# MicroMod_Processor_Board-nRF52840.net
KiCad netlist of a schematic drawn in EAGLE
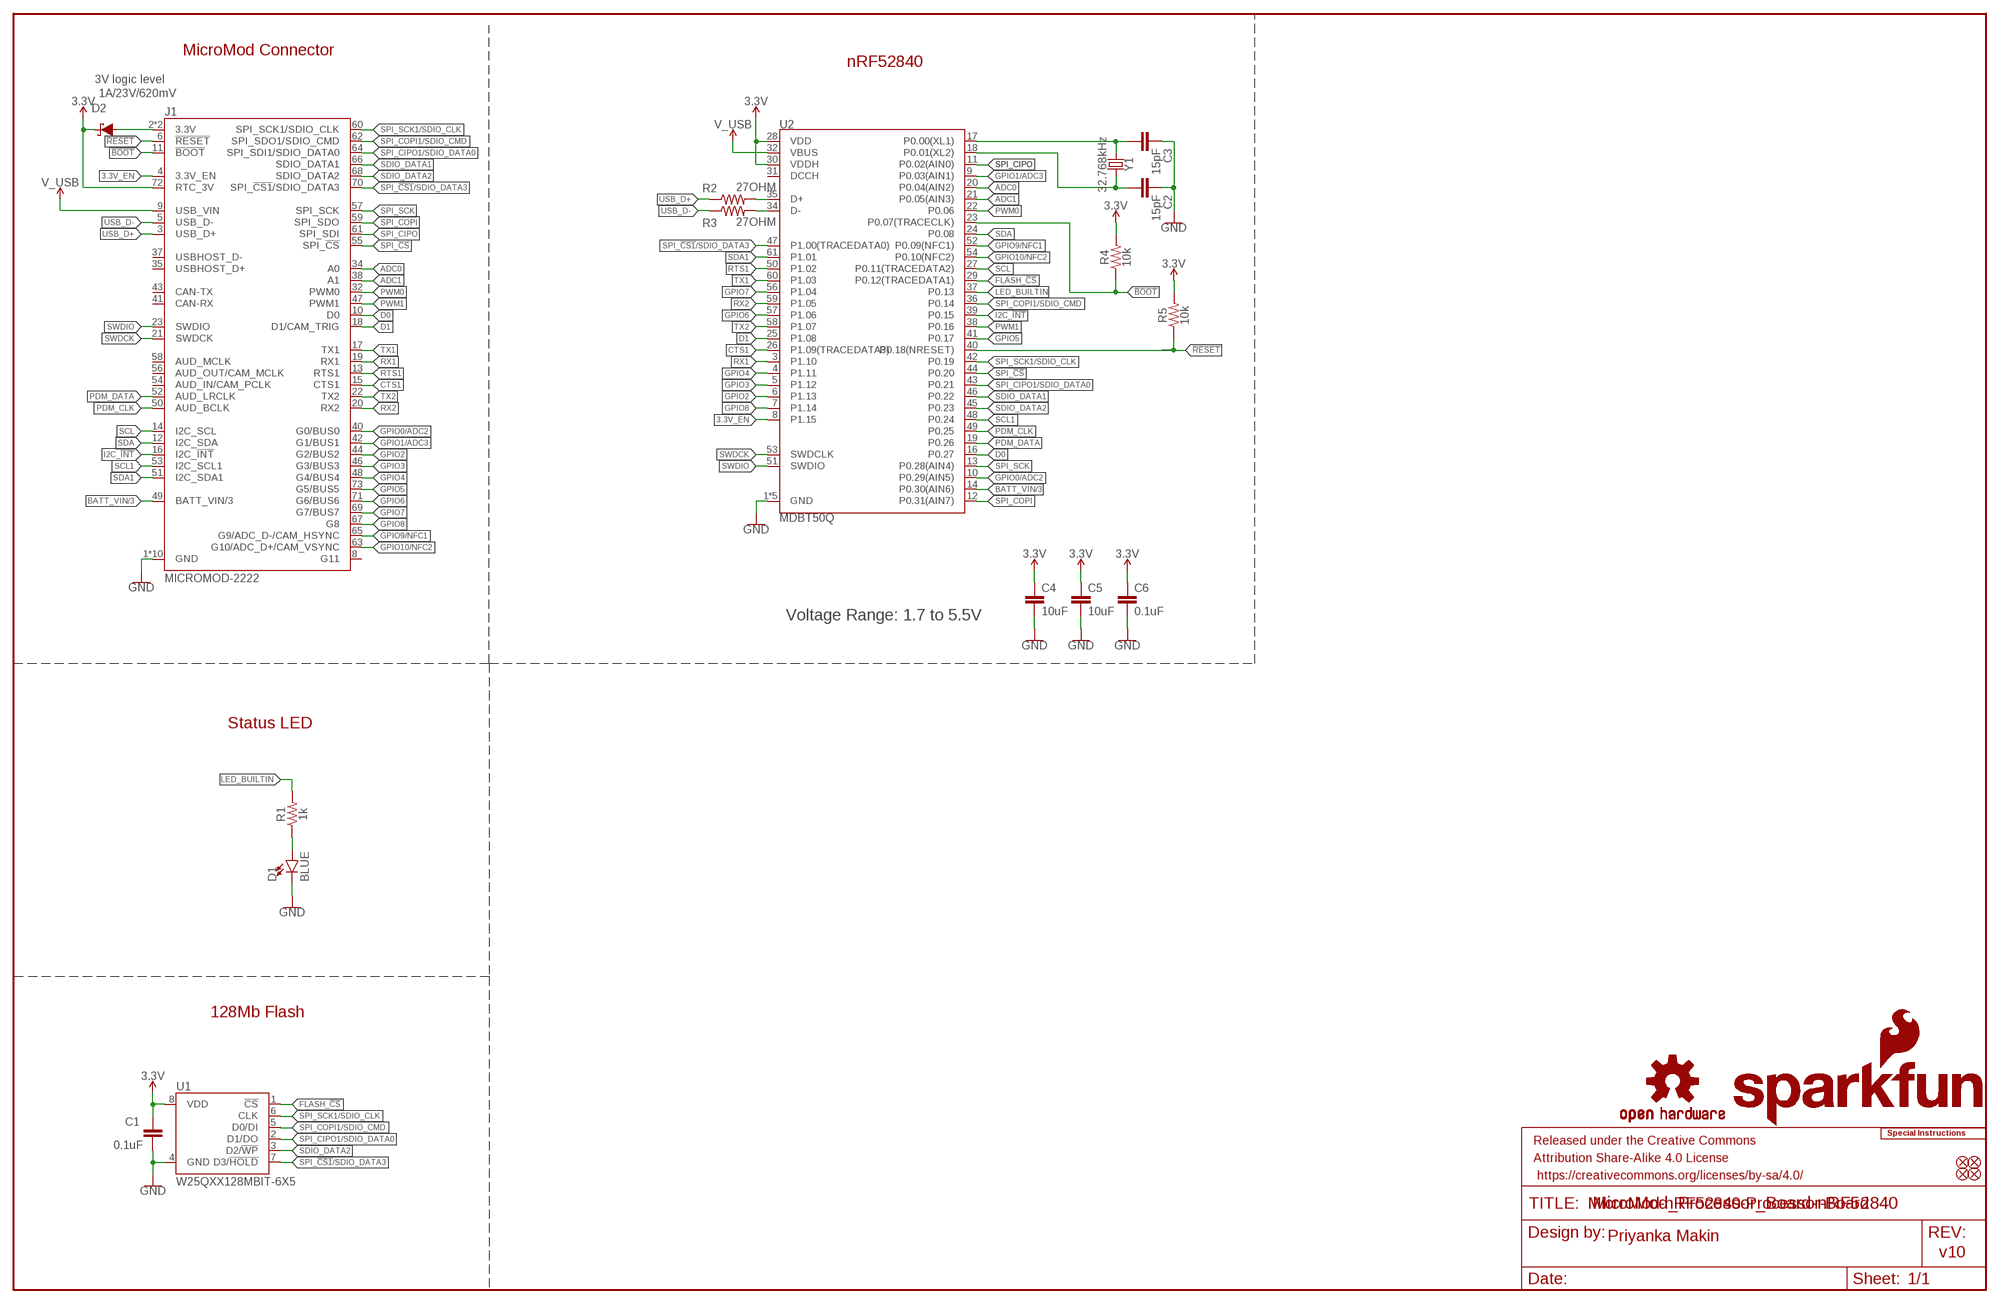
[diagram p0: schematic, sheet 1]

(export (version "E")
  (design (tool "Eeschema 10.0.6"))
  (components
    (comp (ref "C1")
      (value "0.1uF")
      (footprint "eagle-import:0402-TIGHT")
      (libsource (lib "eagle-import") (part "0.1UF-0402T-16V-10%"))
    )
    (comp (ref "C2")
      (value "15pF")
      (footprint "eagle-import:0402-TIGHT")
      (libsource (lib "eagle-import") (part "15PF-0402T-50V-5%"))
    )
    (comp (ref "C3")
      (value "15pF")
      (footprint "eagle-import:0402-TIGHT")
      (libsource (lib "eagle-import") (part "15PF-0402T-50V-5%"))
    )
    (comp (ref "C4")
      (value "10uF")
      (footprint "eagle-import:0402-TIGHT")
      (libsource (lib "eagle-import") (part "10UF-0402T-6.3V-20%"))
    )
    (comp (ref "C5")
      (value "10uF")
      (footprint "eagle-import:0402-TIGHT")
      (libsource (lib "eagle-import") (part "10UF-0402T-6.3V-20%"))
    )
    (comp (ref "C6")
      (value "0.1uF")
      (footprint "eagle-import:0402-TIGHT")
      (libsource (lib "eagle-import") (part "0.1UF-0402T-16V-10%"))
    )
    (comp (ref "D1")
      (value "BLUE")
      (footprint "eagle-import:LED-0603")
      (libsource (lib "eagle-import") (part "LED-BLUE0603"))
    )
    (comp (ref "D2")
      (value "1A/23V/620mV")
      (footprint "eagle-import:SOD-323")
      (libsource (lib "eagle-import") (part "DIODE-SCHOTTKY-BAT20J"))
    )
    (comp (ref "FD1")
      (value "FIDUCIALUFIDUCIAL")
      (footprint "eagle-import:FIDUCIAL-MICRO")
      (libsource (lib "eagle-import") (part "FIDUCIALUFIDUCIAL"))
    )
    (comp (ref "FD2")
      (value "FIDUCIALUFIDUCIAL")
      (footprint "eagle-import:FIDUCIAL-MICRO")
      (libsource (lib "eagle-import") (part "FIDUCIALUFIDUCIAL"))
    )
    (comp (ref "FD3")
      (value "FIDUCIALUFIDUCIAL")
      (footprint "eagle-import:FIDUCIAL-MICRO")
      (libsource (lib "eagle-import") (part "FIDUCIALUFIDUCIAL"))
    )
    (comp (ref "FD4")
      (value "FIDUCIALUFIDUCIAL")
      (footprint "eagle-import:FIDUCIAL-MICRO")
      (libsource (lib "eagle-import") (part "FIDUCIALUFIDUCIAL"))
    )
    (comp (ref "FRAME1")
      (value "FRAME-LEDGER")
      (footprint "eagle-import:CREATIVE_COMMONS")
      (libsource (lib "eagle-import") (part "FRAME-LEDGER"))
    )
    (comp (ref "J1")
      (value "MICROMOD-2222")
      (footprint "eagle-import:M.2-CARD-E-22")
      (libsource (lib "eagle-import") (part "MICROMOD-2222"))
    )
    (comp (ref "LOGO1")
      (value "SFE_LOGO_NAME_FLAME.1_INCH")
      (footprint "eagle-import:SFE_LOGO_NAME_FLAME_.1")
      (libsource (lib "eagle-import") (part "SFE_LOGO_NAME_FLAME.1_INCH"))
    )
    (comp (ref "LOGO2")
      (value "SFE_LOGO_FLAME.1_INCH")
      (footprint "eagle-import:SFE_LOGO_FLAME_.1")
      (libsource (lib "eagle-import") (part "SFE_LOGO_FLAME.1_INCH"))
    )
    (comp (ref "LOGO3")
      (value "OSHW-LOGOMINI")
      (footprint "eagle-import:OSHW-LOGO-MINI")
      (libsource (lib "eagle-import") (part "OSHW-LOGOMINI"))
    )
    (comp (ref "LOGO4")
      (value "SPECIAL_INSTRUCTIONS-ORDERING")
      (footprint "eagle-import:ORDERING_INSTRUCTIONS")
      (libsource (lib "eagle-import") (part "SPECIAL_INSTRUCTIONS-ORDERING"))
    )
    (comp (ref "R1")
      (value "1k")
      (footprint "eagle-import:0402-TIGHT")
      (libsource (lib "eagle-import") (part "1KOHM-0402T-1/16W-1%"))
    )
    (comp (ref "R2")
      (value "27OHM")
      (footprint "eagle-import:0402-TIGHT")
      (libsource (lib "eagle-import") (part "27OHM"))
    )
    (comp (ref "R3")
      (value "27OHM")
      (footprint "eagle-import:0402-TIGHT")
      (libsource (lib "eagle-import") (part "27OHM"))
    )
    (comp (ref "R4")
      (value "10k")
      (footprint "eagle-import:0402-TIGHT")
      (libsource (lib "eagle-import") (part "10KOHM-0402T-1/16W-1%"))
    )
    (comp (ref "R5")
      (value "10k")
      (footprint "eagle-import:0402-TIGHT")
      (libsource (lib "eagle-import") (part "10KOHM-0402T-1/16W-1%"))
    )
    (comp (ref "U1")
      (value "W25QXX128MBIT-6X5")
      (footprint "eagle-import:WSON-8-6X5")
      (libsource (lib "eagle-import") (part "W25QXX128MBIT-6X5"))
    )
    (comp (ref "U2")
      (value "MDBT50Q")
      (footprint "eagle-import:MDBT50Q")
      (libsource (lib "eagle-import") (part "MDBT50Q"))
    )
    (comp (ref "Y1")
      (value "32.768kHz")
      (footprint "eagle-import:CRYSTAL-SMD-3.2X1.5MM")
      (libsource (lib "eagle-import") (part "CRYSTAL-32.768KHZSMD-3.2X1.5"))
    )
  )
  (nets
    (net (code "1") (name "/FLASH_~{CS}") (class "Default")
      (node (ref "U1") (pin "1") (pinfunction "~{CS}_1") (pintype "bidirectional"))
      (node (ref "U2") (pin "29") (pinfunction "P0.12(TRACEDATA1)_29") (pintype "bidirectional"))
    )
    (net (code "2") (name "/I2C_~{INT}") (class "Default")
      (node (ref "J1") (pin "16") (pinfunction "I2C_~{INT}_16") (pintype "bidirectional"))
      (node (ref "U2") (pin "39") (pinfunction "P0.15_39") (pintype "bidirectional"))
    )
    (net (code "3") (name "/SPI_~{CS1}{slash}SDIO_DATA3") (class "Default")
      (node (ref "J1") (pin "70") (pinfunction "SPI_~{CS1}/SDIO_DATA3_70") (pintype "bidirectional"))
      (node (ref "U1") (pin "7") (pinfunction "D3/~{HOLD}_7") (pintype "bidirectional"))
      (node (ref "U2") (pin "47") (pinfunction "P1.00(TRACEDATA0)_47") (pintype "bidirectional"))
    )
    (net (code "4") (name "/SPI_~{CS}") (class "Default")
      (node (ref "J1") (pin "55") (pinfunction "SPI_~{CS}_55") (pintype "bidirectional"))
      (node (ref "U2") (pin "44") (pinfunction "P0.20_44") (pintype "bidirectional"))
    )
    (net (code "5") (name "/~{BOOT}") (class "Default")
      (node (ref "J1") (pin "11") (pinfunction "~{BOOT}_11") (pintype "bidirectional"))
      (node (ref "R4") (pin "1") (pinfunction "1_1") (pintype "passive"))
      (node (ref "U2") (pin "23") (pinfunction "P0.07(TRACECLK)_23") (pintype "bidirectional"))
    )
    (net (code "6") (name "/~{RESET}") (class "Default")
      (node (ref "J1") (pin "6") (pinfunction "~{RESET}_6") (pintype "bidirectional"))
      (node (ref "R5") (pin "1") (pinfunction "1_1") (pintype "passive"))
      (node (ref "U2") (pin "40") (pinfunction "P0.18(NRESET)_40") (pintype "bidirectional"))
    )
    (net (code "7") (name "3.3V") (class "Default")
      (node (ref "C1") (pin "1") (pinfunction "1_1") (pintype "passive"))
      (node (ref "C4") (pin "1") (pinfunction "1_1") (pintype "passive"))
      (node (ref "C5") (pin "1") (pinfunction "1_1") (pintype "passive"))
      (node (ref "C6") (pin "1") (pinfunction "1_1") (pintype "passive"))
      (node (ref "D2") (pin "C") (pinfunction "C_C") (pintype "passive"))
      (node (ref "J1") (pin "72") (pinfunction "RTC_3V_72") (pintype "bidirectional"))
      (node (ref "R4") (pin "2") (pinfunction "2_2") (pintype "passive"))
      (node (ref "R5") (pin "2") (pinfunction "2_2") (pintype "passive"))
      (node (ref "U1") (pin "8") (pinfunction "VDD_8") (pintype "bidirectional"))
      (node (ref "U2") (pin "28") (pinfunction "VDD_28") (pintype "bidirectional"))
      (node (ref "U2") (pin "30") (pinfunction "VDDH_30") (pintype "bidirectional"))
    )
    (net (code "8") (name "3.3V_EN") (class "Default")
      (node (ref "J1") (pin "4") (pinfunction "3.3V_EN_4") (pintype "bidirectional"))
      (node (ref "U2") (pin "8") (pinfunction "P1.15_8") (pintype "bidirectional"))
    )
    (net (code "9") (name "ADC0") (class "Default")
      (node (ref "J1") (pin "34") (pinfunction "A0_34") (pintype "bidirectional"))
      (node (ref "U2") (pin "20") (pinfunction "P0.04(AIN2)_20") (pintype "bidirectional"))
    )
    (net (code "10") (name "ADC1") (class "Default")
      (node (ref "J1") (pin "38") (pinfunction "A1_38") (pintype "bidirectional"))
      (node (ref "U2") (pin "21") (pinfunction "P0.05(AIN3)_21") (pintype "bidirectional"))
    )
    (net (code "11") (name "BATT_VIN{slash}3") (class "Default")
      (node (ref "J1") (pin "49") (pinfunction "BATT_VIN/3_49") (pintype "bidirectional"))
      (node (ref "U2") (pin "14") (pinfunction "P0.30(AIN6)_14") (pintype "bidirectional"))
    )
    (net (code "12") (name "CTS1") (class "Default")
      (node (ref "J1") (pin "15") (pinfunction "CTS1_15") (pintype "bidirectional"))
      (node (ref "U2") (pin "26") (pinfunction "P1.09(TRACEDATA3)_26") (pintype "bidirectional"))
    )
    (net (code "13") (name "D0") (class "Default")
      (node (ref "J1") (pin "10") (pinfunction "D0_10") (pintype "bidirectional"))
      (node (ref "U2") (pin "16") (pinfunction "P0.27_16") (pintype "bidirectional"))
    )
    (net (code "14") (name "D1") (class "Default")
      (node (ref "J1") (pin "18") (pinfunction "D1/CAM_TRIG_18") (pintype "bidirectional"))
      (node (ref "U2") (pin "25") (pinfunction "P1.08_25") (pintype "bidirectional"))
    )
    (net (code "15") (name "GND") (class "Default")
      (node (ref "C1") (pin "2") (pinfunction "2_2") (pintype "passive"))
      (node (ref "C2") (pin "1") (pinfunction "1_1") (pintype "passive"))
      (node (ref "C3") (pin "1") (pinfunction "1_1") (pintype "passive"))
      (node (ref "C4") (pin "2") (pinfunction "2_2") (pintype "passive"))
      (node (ref "C5") (pin "2") (pinfunction "2_2") (pintype "passive"))
      (node (ref "C6") (pin "2") (pinfunction "2_2") (pintype "passive"))
      (node (ref "D1") (pin "C") (pinfunction "C_C") (pintype "passive"))
      (node (ref "J1") (pin "1") (pinfunction "GND_1") (pintype "bidirectional"))
      (node (ref "J1") (pin "33") (pinfunction "GND_33") (pintype "bidirectional"))
      (node (ref "J1") (pin "36") (pinfunction "GND_36") (pintype "bidirectional"))
      (node (ref "J1") (pin "39") (pinfunction "GND_39") (pintype "bidirectional"))
      (node (ref "J1") (pin "45") (pinfunction "GND_45") (pintype "bidirectional"))
      (node (ref "J1") (pin "7") (pinfunction "GND_7") (pintype "bidirectional"))
      (node (ref "J1") (pin "75") (pinfunction "GND_75") (pintype "bidirectional"))
      (node (ref "J1") (pin "GND1") (pinfunction "GND_GND1") (pintype "bidirectional"))
      (node (ref "J1") (pin "GND2") (pinfunction "GND_GND2") (pintype "bidirectional"))
      (node (ref "J1") (pin "GND3") (pinfunction "GND_GND3") (pintype "bidirectional"))
      (node (ref "U1") (pin "4") (pinfunction "GND_4") (pintype "bidirectional"))
      (node (ref "U2") (pin "1") (pinfunction "GND_1") (pintype "bidirectional"))
      (node (ref "U2") (pin "15") (pinfunction "GND_15") (pintype "bidirectional"))
      (node (ref "U2") (pin "2") (pinfunction "GND_2") (pintype "bidirectional"))
      (node (ref "U2") (pin "33") (pinfunction "GND_33") (pintype "bidirectional"))
      (node (ref "U2") (pin "55") (pinfunction "GND_55") (pintype "bidirectional"))
    )
    (net (code "16") (name "GPIO0{slash}ADC2") (class "Default")
      (node (ref "J1") (pin "40") (pinfunction "G0/BUS0_40") (pintype "bidirectional"))
      (node (ref "U2") (pin "10") (pinfunction "P0.29(AIN5)_10") (pintype "bidirectional"))
    )
    (net (code "17") (name "GPIO1{slash}ADC3") (class "Default")
      (node (ref "J1") (pin "42") (pinfunction "G1/BUS1_42") (pintype "bidirectional"))
      (node (ref "U2") (pin "9") (pinfunction "P0.03(AIN1)_9") (pintype "bidirectional"))
    )
    (net (code "18") (name "GPIO2") (class "Default")
      (node (ref "J1") (pin "44") (pinfunction "G2/BUS2_44") (pintype "bidirectional"))
      (node (ref "U2") (pin "6") (pinfunction "P1.13_6") (pintype "bidirectional"))
    )
    (net (code "19") (name "GPIO3") (class "Default")
      (node (ref "J1") (pin "46") (pinfunction "G3/BUS3_46") (pintype "bidirectional"))
      (node (ref "U2") (pin "5") (pinfunction "P1.12_5") (pintype "bidirectional"))
    )
    (net (code "20") (name "GPIO4") (class "Default")
      (node (ref "J1") (pin "48") (pinfunction "G4/BUS4_48") (pintype "bidirectional"))
      (node (ref "U2") (pin "4") (pinfunction "P1.11_4") (pintype "bidirectional"))
    )
    (net (code "21") (name "GPIO5") (class "Default")
      (node (ref "J1") (pin "73") (pinfunction "G5/BUS5_73") (pintype "bidirectional"))
      (node (ref "U2") (pin "41") (pinfunction "P0.17_41") (pintype "bidirectional"))
    )
    (net (code "22") (name "GPIO6") (class "Default")
      (node (ref "J1") (pin "71") (pinfunction "G6/BUS6_71") (pintype "bidirectional"))
      (node (ref "U2") (pin "57") (pinfunction "P1.06_57") (pintype "bidirectional"))
    )
    (net (code "23") (name "GPIO7") (class "Default")
      (node (ref "J1") (pin "69") (pinfunction "G7/BUS7_69") (pintype "bidirectional"))
      (node (ref "U2") (pin "56") (pinfunction "P1.04_56") (pintype "bidirectional"))
    )
    (net (code "24") (name "GPIO8") (class "Default")
      (node (ref "J1") (pin "67") (pinfunction "G8_67") (pintype "bidirectional"))
      (node (ref "U2") (pin "7") (pinfunction "P1.14_7") (pintype "bidirectional"))
    )
    (net (code "25") (name "GPIO9{slash}NFC1") (class "Default")
      (node (ref "J1") (pin "65") (pinfunction "G9/ADC_D-/CAM_HSYNC_65") (pintype "bidirectional"))
      (node (ref "U2") (pin "52") (pinfunction "P0.09(NFC1)_52") (pintype "bidirectional"))
    )
    (net (code "26") (name "GPIO10{slash}NFC2") (class "Default")
      (node (ref "J1") (pin "63") (pinfunction "G10/ADC_D+/CAM_VSYNC_63") (pintype "bidirectional"))
      (node (ref "U2") (pin "54") (pinfunction "P0.10(NFC2)_54") (pintype "bidirectional"))
    )
    (net (code "27") (name "LED_BUILTIN") (class "Default")
      (node (ref "R1") (pin "2") (pinfunction "2_2") (pintype "passive"))
      (node (ref "U2") (pin "37") (pinfunction "P0.13_37") (pintype "bidirectional"))
    )
    (net (code "28") (name "Net-(D1-PadA)") (class "Default")
      (node (ref "D1") (pin "A") (pinfunction "A_A") (pintype "passive"))
      (node (ref "R1") (pin "1") (pinfunction "1_1") (pintype "passive"))
    )
    (net (code "29") (name "Net-(D2-PadA)") (class "Default")
      (node (ref "D2") (pin "A") (pinfunction "A_A") (pintype "passive"))
      (node (ref "J1") (pin "2") (pinfunction "3.3V_2") (pintype "bidirectional"))
      (node (ref "J1") (pin "74") (pinfunction "3.3V_74") (pintype "bidirectional"))
    )
    (net (code "30") (name "Net-(U2-D+)") (class "Default")
      (node (ref "R2") (pin "2") (pinfunction "2_2") (pintype "passive"))
      (node (ref "U2") (pin "35") (pinfunction "D+_35") (pintype "bidirectional"))
    )
    (net (code "31") (name "Net-(U2-D-)") (class "Default")
      (node (ref "R3") (pin "2") (pinfunction "2_2") (pintype "passive"))
      (node (ref "U2") (pin "34") (pinfunction "D-_34") (pintype "bidirectional"))
    )
    (net (code "32") (name "Net-(U2-P0.00(XL1))") (class "Default")
      (node (ref "C3") (pin "2") (pinfunction "2_2") (pintype "passive"))
      (node (ref "U2") (pin "17") (pinfunction "P0.00(XL1)_17") (pintype "bidirectional"))
      (node (ref "Y1") (pin "P$1") (pinfunction "1_P$1") (pintype "passive"))
    )
    (net (code "33") (name "Net-(U2-P0.01(XL2))") (class "Default")
      (node (ref "C2") (pin "2") (pinfunction "2_2") (pintype "passive"))
      (node (ref "U2") (pin "18") (pinfunction "P0.01(XL2)_18") (pintype "bidirectional"))
      (node (ref "Y1") (pin "P$2") (pinfunction "2_P$2") (pintype "passive"))
    )
    (net (code "34") (name "PDM_CLK") (class "Default")
      (node (ref "J1") (pin "50") (pinfunction "AUD_BCLK_50") (pintype "bidirectional"))
      (node (ref "U2") (pin "49") (pinfunction "P0.25_49") (pintype "bidirectional"))
    )
    (net (code "35") (name "PDM_DATA") (class "Default")
      (node (ref "J1") (pin "52") (pinfunction "AUD_LRCLK_52") (pintype "bidirectional"))
      (node (ref "U2") (pin "19") (pinfunction "P0.26_19") (pintype "bidirectional"))
    )
    (net (code "36") (name "PWM0") (class "Default")
      (node (ref "J1") (pin "32") (pinfunction "PWM0_32") (pintype "bidirectional"))
      (node (ref "U2") (pin "22") (pinfunction "P0.06_22") (pintype "bidirectional"))
    )
    (net (code "37") (name "PWM1") (class "Default")
      (node (ref "J1") (pin "47") (pinfunction "PWM1_47") (pintype "bidirectional"))
      (node (ref "U2") (pin "38") (pinfunction "P0.16_38") (pintype "bidirectional"))
    )
    (net (code "38") (name "RTS1") (class "Default")
      (node (ref "J1") (pin "13") (pinfunction "RTS1_13") (pintype "bidirectional"))
      (node (ref "U2") (pin "50") (pinfunction "P1.02_50") (pintype "bidirectional"))
    )
    (net (code "39") (name "RX1") (class "Default")
      (node (ref "J1") (pin "19") (pinfunction "RX1_19") (pintype "bidirectional"))
      (node (ref "U2") (pin "3") (pinfunction "P1.10_3") (pintype "bidirectional"))
    )
    (net (code "40") (name "RX2") (class "Default")
      (node (ref "J1") (pin "20") (pinfunction "RX2_20") (pintype "bidirectional"))
      (node (ref "U2") (pin "59") (pinfunction "P1.05_59") (pintype "bidirectional"))
    )
    (net (code "41") (name "SCL") (class "Default")
      (node (ref "J1") (pin "14") (pinfunction "I2C_SCL_14") (pintype "bidirectional"))
      (node (ref "U2") (pin "27") (pinfunction "P0.11(TRACEDATA2)_27") (pintype "bidirectional"))
    )
    (net (code "42") (name "SCL1") (class "Default")
      (node (ref "J1") (pin "53") (pinfunction "I2C_SCL1_53") (pintype "bidirectional"))
      (node (ref "U2") (pin "48") (pinfunction "P0.24_48") (pintype "bidirectional"))
    )
    (net (code "43") (name "SDA") (class "Default")
      (node (ref "J1") (pin "12") (pinfunction "I2C_SDA_12") (pintype "bidirectional"))
      (node (ref "U2") (pin "24") (pinfunction "P0.08_24") (pintype "bidirectional"))
    )
    (net (code "44") (name "SDA1") (class "Default")
      (node (ref "J1") (pin "51") (pinfunction "I2C_SDA1_51") (pintype "bidirectional"))
      (node (ref "U2") (pin "61") (pinfunction "P1.01_61") (pintype "bidirectional"))
    )
    (net (code "45") (name "SDIO_DATA1") (class "Default")
      (node (ref "J1") (pin "66") (pinfunction "SDIO_DATA1_66") (pintype "bidirectional"))
      (node (ref "U2") (pin "46") (pinfunction "P0.22_46") (pintype "bidirectional"))
    )
    (net (code "46") (name "SDIO_DATA2") (class "Default")
      (node (ref "J1") (pin "68") (pinfunction "SDIO_DATA2_68") (pintype "bidirectional"))
      (node (ref "U1") (pin "3") (pinfunction "D2/~{WP}_3") (pintype "bidirectional"))
      (node (ref "U2") (pin "45") (pinfunction "P0.23_45") (pintype "bidirectional"))
    )
    (net (code "47") (name "SPI_CIPO") (class "Default")
      (node (ref "J1") (pin "61") (pinfunction "SPI_SDI_61") (pintype "bidirectional"))
      (node (ref "U2") (pin "11") (pinfunction "P0.02(AIN0)_11") (pintype "bidirectional"))
    )
    (net (code "48") (name "SPI_CIPO1{slash}SDIO_DATA0") (class "Default")
      (node (ref "J1") (pin "64") (pinfunction "SPI_SDI1/SDIO_DATA0_64") (pintype "bidirectional"))
      (node (ref "U1") (pin "2") (pinfunction "D1/DO_2") (pintype "bidirectional"))
      (node (ref "U2") (pin "43") (pinfunction "P0.21_43") (pintype "bidirectional"))
    )
    (net (code "49") (name "SPI_COPI") (class "Default")
      (node (ref "J1") (pin "59") (pinfunction "SPI_SDO_59") (pintype "bidirectional"))
      (node (ref "U2") (pin "12") (pinfunction "P0.31(AIN7)_12") (pintype "bidirectional"))
    )
    (net (code "50") (name "SPI_COPI1{slash}SDIO_CMD") (class "Default")
      (node (ref "J1") (pin "62") (pinfunction "SPI_SDO1/SDIO_CMD_62") (pintype "bidirectional"))
      (node (ref "U1") (pin "5") (pinfunction "D0/DI_5") (pintype "bidirectional"))
      (node (ref "U2") (pin "36") (pinfunction "P0.14_36") (pintype "bidirectional"))
    )
    (net (code "51") (name "SPI_SCK") (class "Default")
      (node (ref "J1") (pin "57") (pinfunction "SPI_SCK_57") (pintype "bidirectional"))
      (node (ref "U2") (pin "13") (pinfunction "P0.28(AIN4)_13") (pintype "bidirectional"))
    )
    (net (code "52") (name "SPI_SCK1{slash}SDIO_CLK") (class "Default")
      (node (ref "J1") (pin "60") (pinfunction "SPI_SCK1/SDIO_CLK_60") (pintype "bidirectional"))
      (node (ref "U1") (pin "6") (pinfunction "CLK_6") (pintype "bidirectional"))
      (node (ref "U2") (pin "42") (pinfunction "P0.19_42") (pintype "bidirectional"))
    )
    (net (code "53") (name "SWDCK") (class "Default")
      (node (ref "J1") (pin "21") (pinfunction "SWDCK_21") (pintype "bidirectional"))
      (node (ref "U2") (pin "53") (pinfunction "SWDCLK_53") (pintype "bidirectional"))
    )
    (net (code "54") (name "SWDIO") (class "Default")
      (node (ref "J1") (pin "23") (pinfunction "SWDIO_23") (pintype "bidirectional"))
      (node (ref "U2") (pin "51") (pinfunction "SWDIO_51") (pintype "bidirectional"))
    )
    (net (code "55") (name "TX1") (class "Default")
      (node (ref "J1") (pin "17") (pinfunction "TX1_17") (pintype "bidirectional"))
      (node (ref "U2") (pin "60") (pinfunction "P1.03_60") (pintype "bidirectional"))
    )
    (net (code "56") (name "TX2") (class "Default")
      (node (ref "J1") (pin "22") (pinfunction "TX2_22") (pintype "bidirectional"))
      (node (ref "U2") (pin "58") (pinfunction "P1.07_58") (pintype "bidirectional"))
    )
    (net (code "57") (name "USB_D+") (class "Default")
      (node (ref "J1") (pin "3") (pinfunction "USB_D+_3") (pintype "bidirectional"))
      (node (ref "R2") (pin "1") (pinfunction "1_1") (pintype "passive"))
    )
    (net (code "58") (name "USB_D-") (class "Default")
      (node (ref "J1") (pin "5") (pinfunction "USB_D-_5") (pintype "bidirectional"))
      (node (ref "R3") (pin "1") (pinfunction "1_1") (pintype "passive"))
    )
    (net (code "59") (name "V_USB") (class "Default")
      (node (ref "J1") (pin "9") (pinfunction "USB_VIN_9") (pintype "bidirectional"))
      (node (ref "U2") (pin "32") (pinfunction "VBUS_32") (pintype "bidirectional"))
    )
    (net (code "60") (name "unconnected-(J1-AUD_IN{slash}CAM_PCLK-Pad54)") (class "Default")
      (node (ref "J1") (pin "54") (pinfunction "AUD_IN/CAM_PCLK_54") (pintype "bidirectional"))
    )
    (net (code "61") (name "unconnected-(J1-AUD_MCLK-Pad58)") (class "Default")
      (node (ref "J1") (pin "58") (pinfunction "AUD_MCLK_58") (pintype "bidirectional"))
    )
    (net (code "62") (name "unconnected-(J1-AUD_OUT{slash}CAM_MCLK-Pad56)") (class "Default")
      (node (ref "J1") (pin "56") (pinfunction "AUD_OUT/CAM_MCLK_56") (pintype "bidirectional"))
    )
    (net (code "63") (name "unconnected-(J1-CAN-RX-Pad41)") (class "Default")
      (node (ref "J1") (pin "41") (pinfunction "CAN-RX_41") (pintype "bidirectional"))
    )
    (net (code "64") (name "unconnected-(J1-CAN-TX-Pad43)") (class "Default")
      (node (ref "J1") (pin "43") (pinfunction "CAN-TX_43") (pintype "bidirectional"))
    )
    (net (code "65") (name "unconnected-(J1-G11-Pad8)") (class "Default")
      (node (ref "J1") (pin "8") (pinfunction "G11_8") (pintype "bidirectional"))
    )
    (net (code "66") (name "unconnected-(J1-USBHOST_D+-Pad35)") (class "Default")
      (node (ref "J1") (pin "35") (pinfunction "USBHOST_D+_35") (pintype "bidirectional"))
    )
    (net (code "67") (name "unconnected-(J1-USBHOST_D--Pad37)") (class "Default")
      (node (ref "J1") (pin "37") (pinfunction "USBHOST_D-_37") (pintype "bidirectional"))
    )
    (net (code "68") (name "unconnected-(U2-DCCH-Pad31)") (class "Default")
      (node (ref "U2") (pin "31") (pinfunction "DCCH_31") (pintype "bidirectional"))
    )
  )
)
